# SeguidorC1_0.net
KiCad netlist of a schematic drawn in EAGLE
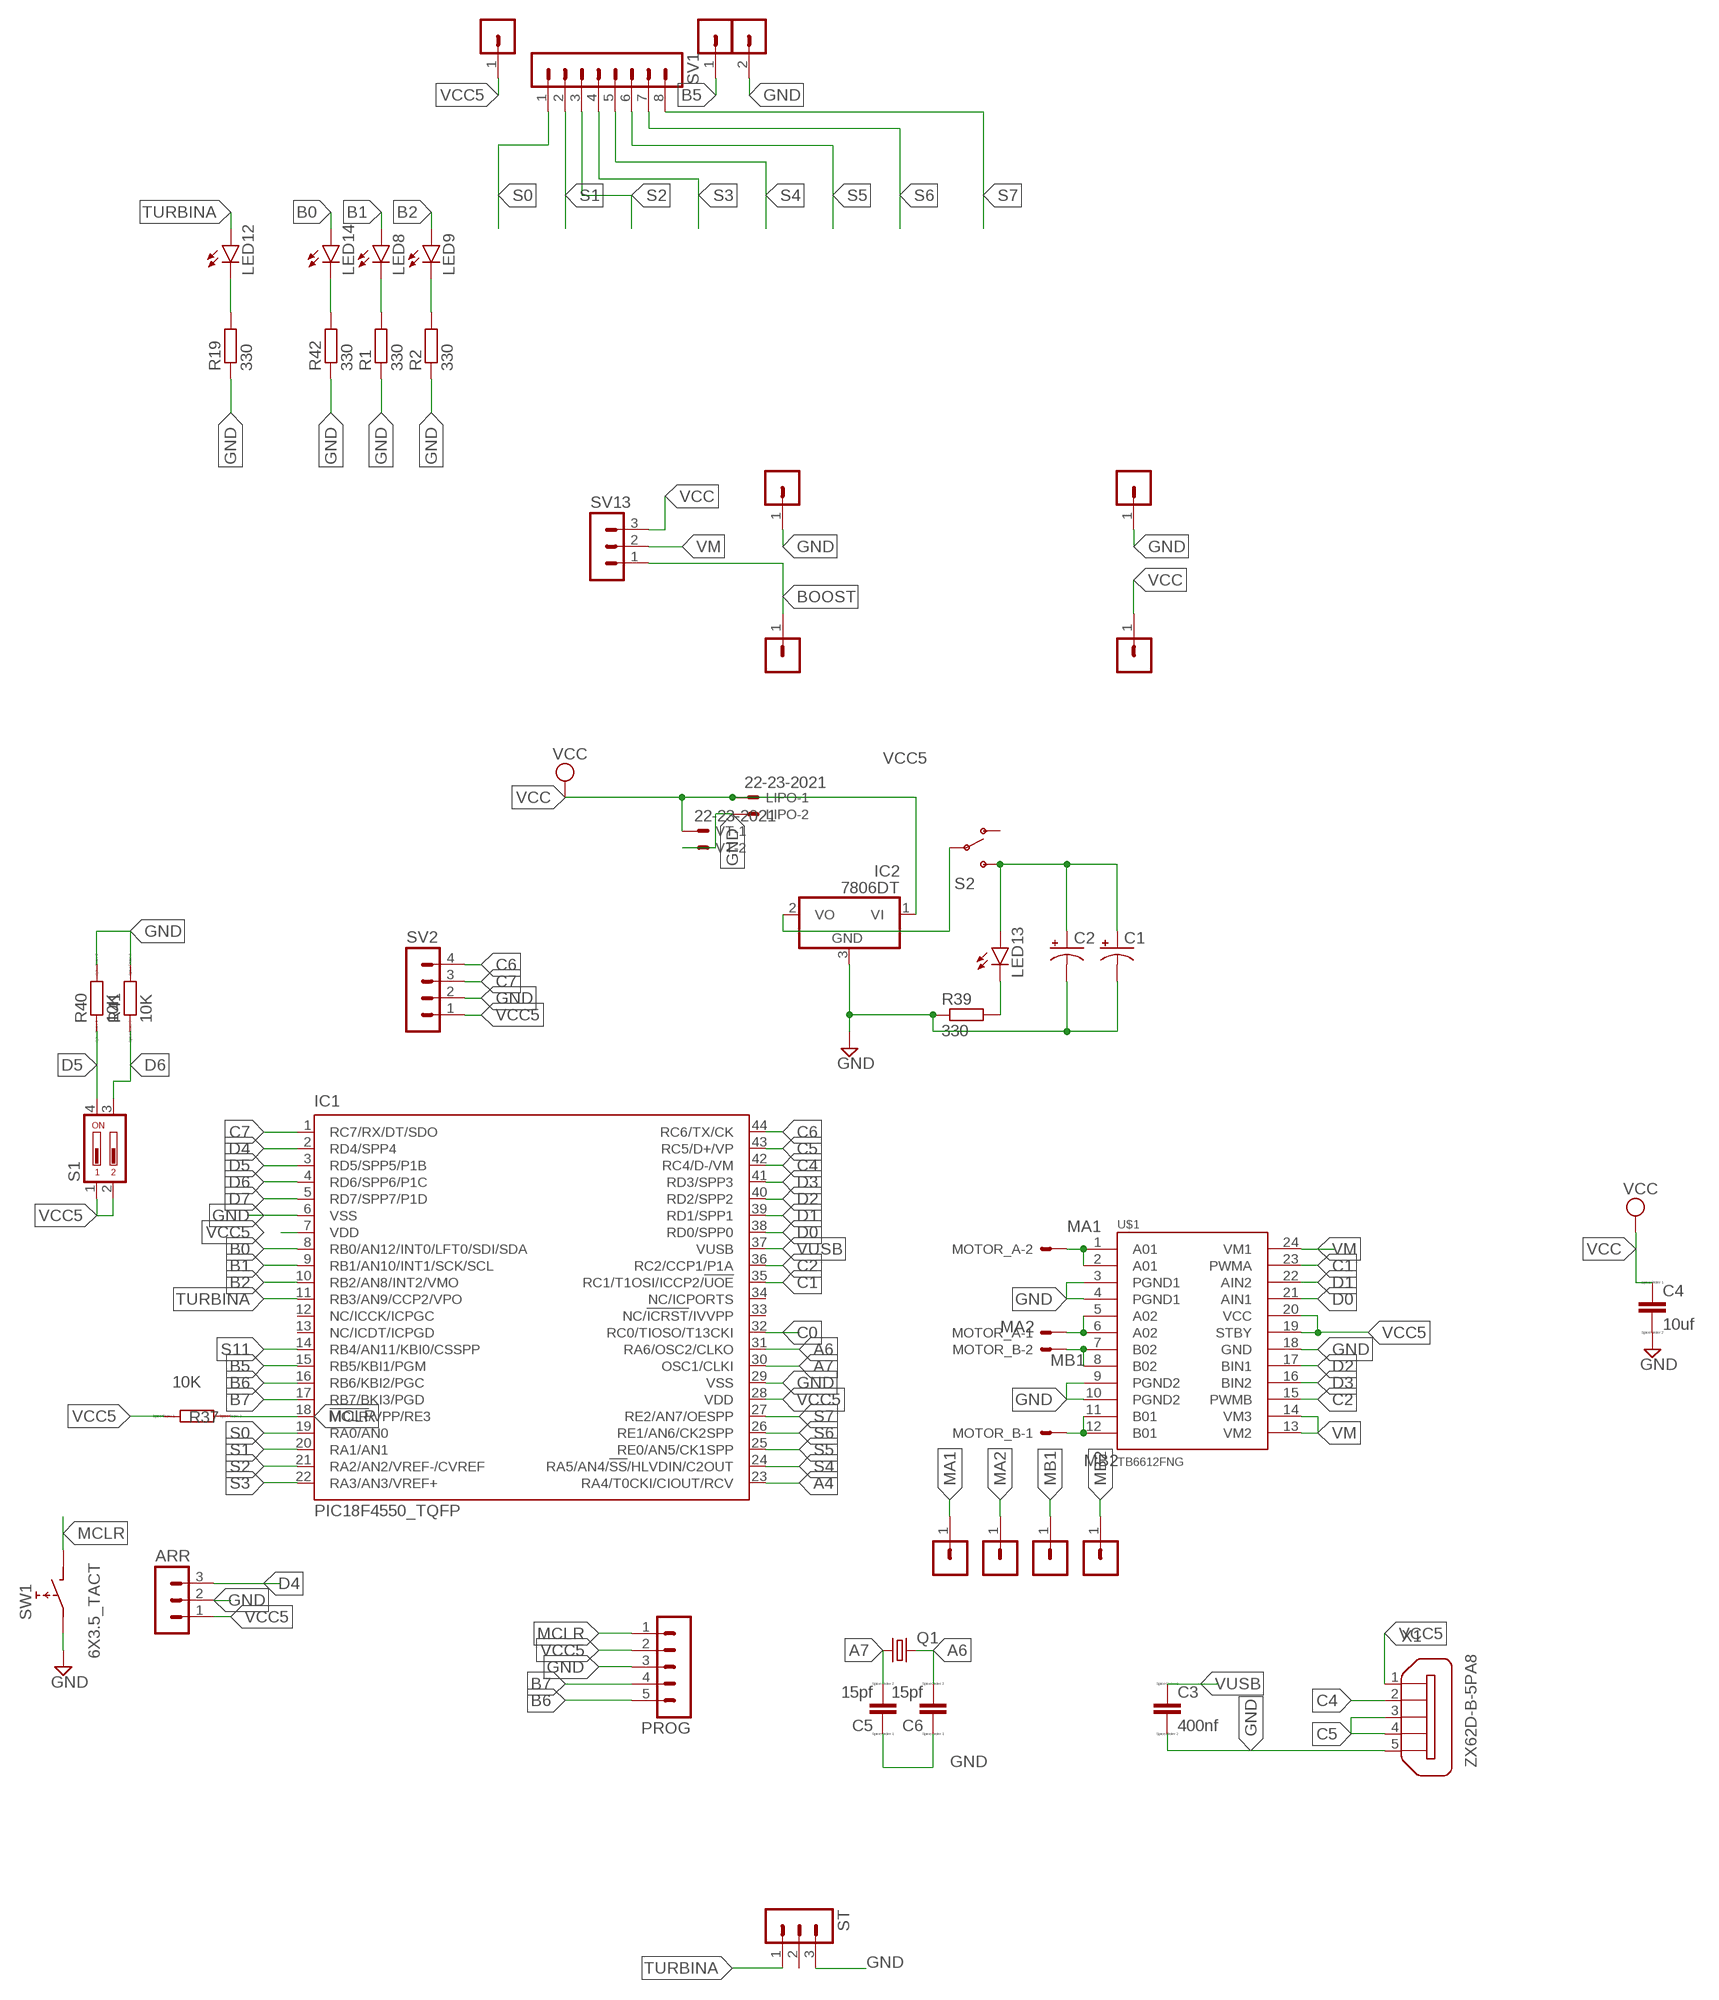
[diagram p0: schematic, sheet 1]

(export (version "E")
  (design (tool "Eeschema 10.0.6"))
  (components
    (comp (ref "ARR")
      (value "MA03-1")
      (footprint "eagle-import:MA03-1")
      (libsource (lib "eagle-import") (part "con-lstb_162_MA03-1"))
    )
    (comp (ref "C1")
      (value "CPOL-US153CLV-0505")
      (footprint "eagle-import:153CLV-0505")
      (libsource (lib "eagle-import") (part "CPOL-US153CLV-0505"))
    )
    (comp (ref "C2")
      (value "CPOL-US153CLV-0505")
      (footprint "eagle-import:153CLV-0505")
      (libsource (lib "eagle-import") (part "CPOL-US153CLV-0505"))
    )
    (comp (ref "C3")
      (value "400nf")
      (footprint "eagle-import:C0805")
      (libsource (lib "eagle-import") (part "C"))
    )
    (comp (ref "C4")
      (value "10uf")
      (footprint "eagle-import:C0805")
      (libsource (lib "eagle-import") (part "C"))
    )
    (comp (ref "C5")
      (value "15pf")
      (footprint "eagle-import:C0805")
      (libsource (lib "eagle-import") (part "C"))
    )
    (comp (ref "C6")
      (value "15pf")
      (footprint "eagle-import:C0805")
      (libsource (lib "eagle-import") (part "C"))
    )
    (comp (ref "IC1")
      (value "PIC18F4550_TQFP")
      (footprint "eagle-import:TQFP44")
      (fields (field (name "MF") "MICROCHIP") (field (name "MPN") "PIC18F4550-I/PT"))
      (libsource (lib "eagle-import") (part "PIC18F4_TQFP550"))
    )
    (comp (ref "IC2")
      (value "7806DT")
      (footprint "eagle-import:TO252")
      (libsource (lib "eagle-import") (part "78DT06"))
    )
    (comp (ref "LED8")
      (value "LEDCHIP-LED0805")
      (footprint "eagle-import:CHIP-LED0805")
      (libsource (lib "eagle-import") (part "LEDCHIP-LED0805"))
    )
    (comp (ref "LED9")
      (value "LEDCHIP-LED0805")
      (footprint "eagle-import:CHIP-LED0805")
      (libsource (lib "eagle-import") (part "LEDCHIP-LED0805"))
    )
    (comp (ref "LED12")
      (value "LEDCHIP-LED0805")
      (footprint "eagle-import:CHIP-LED0805")
      (libsource (lib "eagle-import") (part "LEDCHIP-LED0805"))
    )
    (comp (ref "LED13")
      (value "LEDCHIP-LED0805")
      (footprint "eagle-import:CHIP-LED0805")
      (libsource (lib "eagle-import") (part "LEDCHIP-LED0805"))
    )
    (comp (ref "LED14")
      (value "LEDCHIP-LED0805")
      (footprint "eagle-import:CHIP-LED0805")
      (libsource (lib "eagle-import") (part "LEDCHIP-LED0805"))
    )
    (comp (ref "LIPO")
      (value "22-23-2021")
      (footprint "eagle-import:22-23-2021")
      (fields (field (name "MF") "MOLEX"))
      (libsource (lib "eagle-import") (part "22-23-2021"))
    )
    (comp (ref "MOTOR_A")
      (value "22-23-2021")
      (footprint "eagle-import:22-23-2021")
      (fields (field (name "MF") "MOLEX"))
      (libsource (lib "eagle-import") (part "22-23-2021"))
    )
    (comp (ref "MOTOR_B")
      (value "22-23-2021")
      (footprint "eagle-import:22-23-2021")
      (fields (field (name "MF") "MOLEX"))
      (libsource (lib "eagle-import") (part "22-23-2021"))
    )
    (comp (ref "PROG")
      (value "MA05-1")
      (footprint "eagle-import:MA05-1")
      (libsource (lib "eagle-import") (part "MA05-1"))
    )
    (comp (ref "Q1")
      (value "CRYSTALHC49U-V")
      (footprint "eagle-import:HC49U-V")
      (libsource (lib "eagle-import") (part "CRYSTALHC49U-V"))
    )
    (comp (ref "R1")
      (value "330")
      (footprint "eagle-import:R0805")
      (libsource (lib "eagle-import") (part "R-EU_R0805"))
    )
    (comp (ref "R2")
      (value "330")
      (footprint "eagle-import:R0805")
      (libsource (lib "eagle-import") (part "R-EU_R0805"))
    )
    (comp (ref "R19")
      (value "330")
      (footprint "eagle-import:R0805")
      (libsource (lib "eagle-import") (part "R-EU_R0805"))
    )
    (comp (ref "R37")
      (value "10K")
      (footprint "eagle-import:R0805")
      (libsource (lib "eagle-import") (part "R"))
    )
    (comp (ref "R39")
      (value "330")
      (footprint "eagle-import:R0805")
      (libsource (lib "eagle-import") (part "R-EU_R0805"))
    )
    (comp (ref "R40")
      (value "10K")
      (footprint "eagle-import:R0805")
      (libsource (lib "eagle-import") (part "R"))
    )
    (comp (ref "R41")
      (value "10K")
      (footprint "eagle-import:R0805")
      (libsource (lib "eagle-import") (part "R"))
    )
    (comp (ref "R42")
      (value "330")
      (footprint "eagle-import:R0805")
      (libsource (lib "eagle-import") (part "R-EU_R0805"))
    )
    (comp (ref "S1")
      (value "DIP02YL")
      (footprint "eagle-import:DIP02YL")
      (libsource (lib "eagle-import") (part "DIP02YL"))
    )
    (comp (ref "S2")
      (value "SWITCH-SPSTPTH")
      (footprint "eagle-import:SWITCH-SPDT")
      (libsource (lib "eagle-import") (part "SWITCH-SPSTPTH"))
    )
    (comp (ref "ST")
      (value "MA03-1")
      (footprint "eagle-import:MA03-1")
      (libsource (lib "eagle-import") (part "MA03-1"))
    )
    (comp (ref "SV1")
      (value "MA08-1")
      (footprint "eagle-import:MA08-1")
      (libsource (lib "eagle-import") (part "MA08-1"))
    )
    (comp (ref "SV2")
      (value "MA04-1")
      (footprint "eagle-import:MA04-1")
      (libsource (lib "eagle-import") (part "MA04-1"))
    )
    (comp (ref "SV3")
      (value "MA01-1")
      (footprint "eagle-import:MA01-1")
      (libsource (lib "eagle-import") (part "MA01-1"))
    )
    (comp (ref "SV4")
      (value "MA01-1")
      (footprint "eagle-import:MA01-1")
      (libsource (lib "eagle-import") (part "MA01-1"))
    )
    (comp (ref "SV5")
      (value "MA01-1")
      (footprint "eagle-import:MA01-1")
      (libsource (lib "eagle-import") (part "MA01-1"))
    )
    (comp (ref "SV6")
      (value "MA01-1")
      (footprint "eagle-import:MA01-1")
      (libsource (lib "eagle-import") (part "MA01-1"))
    )
    (comp (ref "SV7")
      (value "MA01-1")
      (footprint "eagle-import:MA01-1")
      (libsource (lib "eagle-import") (part "MA01-1"))
    )
    (comp (ref "SV8")
      (value "MA02-1")
      (footprint "eagle-import:MA02-1")
      (libsource (lib "eagle-import") (part "MA02-1"))
    )
    (comp (ref "SV9")
      (value "MA01-1")
      (footprint "eagle-import:MA01-1")
      (libsource (lib "eagle-import") (part "MA01-1"))
    )
    (comp (ref "SV10")
      (value "MA01-1")
      (footprint "eagle-import:MA01-1")
      (libsource (lib "eagle-import") (part "MA01-1"))
    )
    (comp (ref "SV11")
      (value "MA01-1")
      (footprint "eagle-import:MA01-1")
      (libsource (lib "eagle-import") (part "MA01-1"))
    )
    (comp (ref "SV12")
      (value "MA01-1")
      (footprint "eagle-import:MA01-1")
      (libsource (lib "eagle-import") (part "MA01-1"))
    )
    (comp (ref "SV13")
      (value "MA03-1")
      (footprint "eagle-import:MA03-1")
      (libsource (lib "eagle-import") (part "MA03-1"))
    )
    (comp (ref "SW1")
      (value "6X3.5_TACT")
      (footprint "eagle-import:TACT_6X3.5")
      (libsource (lib "eagle-import") (part "6X3.5_TACT"))
    )
    (comp (ref "U$1")
      (value "TB6612FNG")
      (footprint "eagle-import:SSOP24")
      (libsource (lib "eagle-import") (part "TB6612FNG"))
    )
    (comp (ref "VT")
      (value "22-23-2021")
      (footprint "eagle-import:22-23-2021")
      (fields (field (name "MF") "MOLEX"))
      (libsource (lib "eagle-import") (part "22-23-2021"))
    )
    (comp (ref "X1")
      (value "ZX62D-B-5PA8")
      (footprint "eagle-import:ZX62D-B-5PA8")
      (fields (field (name "MF") "Hirose"))
      (libsource (lib "eagle-import") (part "ZX62D-B-5PA8"))
    )
  )
  (nets
    (net (code "1") (name "A4") (class "Default")
      (node (ref "IC1") (pin "23") (pinfunction "RA4/T0CKI/CIOUT/RCV_23") (pintype "bidirectional"))
    )
    (net (code "2") (name "A6") (class "Default")
      (node (ref "C6") (pin "2") (pinfunction "2_2") (pintype "passive"))
      (node (ref "IC1") (pin "31") (pinfunction "RA6/OSC2/CLKO_31") (pintype "output"))
      (node (ref "Q1") (pin "2") (pinfunction "2_2") (pintype "passive"))
    )
    (net (code "3") (name "A7") (class "Default")
      (node (ref "C5") (pin "2") (pinfunction "2_2") (pintype "passive"))
      (node (ref "IC1") (pin "30") (pinfunction "OSC1/CLKI_30") (pintype "input"))
      (node (ref "Q1") (pin "1") (pinfunction "1_1") (pintype "passive"))
    )
    (net (code "4") (name "B0") (class "Default")
      (node (ref "IC1") (pin "8") (pinfunction "RB0/AN12/INT0/LFT0/SDI/SDA_8") (pintype "bidirectional"))
      (node (ref "LED14") (pin "A") (pinfunction "A_A") (pintype "passive"))
    )
    (net (code "5") (name "B1") (class "Default")
      (node (ref "IC1") (pin "9") (pinfunction "RB1/AN10/INT1/SCK/SCL_9") (pintype "bidirectional"))
      (node (ref "LED8") (pin "A") (pinfunction "A_A") (pintype "passive"))
    )
    (net (code "6") (name "B2") (class "Default")
      (node (ref "IC1") (pin "10") (pinfunction "RB2/AN8/INT2/VMO_10") (pintype "bidirectional"))
      (node (ref "LED9") (pin "A") (pinfunction "A_A") (pintype "passive"))
    )
    (net (code "7") (name "B5") (class "Default")
      (node (ref "IC1") (pin "15") (pinfunction "RB5/KBI1/PGM_15") (pintype "bidirectional"))
      (node (ref "SV8") (pin "1") (pinfunction "1_1") (pintype "passive"))
    )
    (net (code "8") (name "B6") (class "Default")
      (node (ref "IC1") (pin "16") (pinfunction "RB6/KBI2/PGC_16") (pintype "bidirectional"))
      (node (ref "PROG") (pin "5") (pinfunction "5_5") (pintype "passive"))
    )
    (net (code "9") (name "B7") (class "Default")
      (node (ref "IC1") (pin "17") (pinfunction "RB7/BKI3/PGD_17") (pintype "bidirectional"))
      (node (ref "PROG") (pin "4") (pinfunction "4_4") (pintype "passive"))
    )
    (net (code "10") (name "BOOST") (class "Default")
      (node (ref "SV11") (pin "1") (pinfunction "3_1") (pintype "passive"))
      (node (ref "SV13") (pin "1") (pinfunction "1_1") (pintype "passive"))
    )
    (net (code "11") (name "C0") (class "Default")
      (node (ref "IC1") (pin "32") (pinfunction "RC0/TIOSO/T13CKI_32") (pintype "bidirectional"))
    )
    (net (code "12") (name "C1") (class "Default")
      (node (ref "IC1") (pin "35") (pinfunction "RC1/T1OSI/ICCP2/~{UOE}_35") (pintype "bidirectional"))
      (node (ref "U$1") (pin "23") (pinfunction "PWMA_23") (pintype "bidirectional"))
    )
    (net (code "13") (name "C2") (class "Default")
      (node (ref "IC1") (pin "36") (pinfunction "RC2/CCP1/P1A_36") (pintype "bidirectional"))
      (node (ref "U$1") (pin "15") (pinfunction "PWMB_15") (pintype "bidirectional"))
    )
    (net (code "14") (name "C4") (class "Default")
      (node (ref "IC1") (pin "42") (pinfunction "RC4/D-/VM_42") (pintype "bidirectional"))
      (node (ref "X1") (pin "2") (pinfunction "2_2") (pintype "passive"))
    )
    (net (code "15") (name "C5") (class "Default")
      (node (ref "IC1") (pin "43") (pinfunction "RC5/D+/VP_43") (pintype "bidirectional"))
      (node (ref "X1") (pin "3") (pinfunction "3_3") (pintype "passive"))
      (node (ref "X1") (pin "4") (pinfunction "4_4") (pintype "passive"))
    )
    (net (code "16") (name "C6") (class "Default")
      (node (ref "IC1") (pin "44") (pinfunction "RC6/TX/CK_44") (pintype "bidirectional"))
      (node (ref "SV2") (pin "4") (pinfunction "4_4") (pintype "passive"))
    )
    (net (code "17") (name "C7") (class "Default")
      (node (ref "IC1") (pin "1") (pinfunction "RC7/RX/DT/SDO_1") (pintype "bidirectional"))
      (node (ref "SV2") (pin "3") (pinfunction "3_3") (pintype "passive"))
    )
    (net (code "18") (name "D0") (class "Default")
      (node (ref "IC1") (pin "38") (pinfunction "RD0/SPP0_38") (pintype "bidirectional"))
      (node (ref "U$1") (pin "21") (pinfunction "AIN1_21") (pintype "bidirectional"))
    )
    (net (code "19") (name "D1") (class "Default")
      (node (ref "IC1") (pin "39") (pinfunction "RD1/SPP1_39") (pintype "bidirectional"))
      (node (ref "U$1") (pin "22") (pinfunction "AIN2_22") (pintype "bidirectional"))
    )
    (net (code "20") (name "D2") (class "Default")
      (node (ref "IC1") (pin "40") (pinfunction "RD2/SPP2_40") (pintype "bidirectional"))
      (node (ref "U$1") (pin "17") (pinfunction "BIN1_17") (pintype "bidirectional"))
    )
    (net (code "21") (name "D3") (class "Default")
      (node (ref "IC1") (pin "41") (pinfunction "RD3/SPP3_41") (pintype "bidirectional"))
      (node (ref "U$1") (pin "16") (pinfunction "BIN2_16") (pintype "bidirectional"))
    )
    (net (code "22") (name "D4") (class "Default")
      (node (ref "ARR") (pin "3") (pinfunction "3_3") (pintype "passive"))
      (node (ref "IC1") (pin "2") (pinfunction "RD4/SPP4_2") (pintype "bidirectional"))
    )
    (net (code "23") (name "D5") (class "Default")
      (node (ref "IC1") (pin "3") (pinfunction "RD5/SPP5/P1B_3") (pintype "bidirectional"))
      (node (ref "R40") (pin "1") (pinfunction "1_1") (pintype "passive"))
      (node (ref "S1") (pin "4") (pinfunction "4_4") (pintype "passive"))
    )
    (net (code "24") (name "D6") (class "Default")
      (node (ref "IC1") (pin "4") (pinfunction "RD6/SPP6/P1C_4") (pintype "bidirectional"))
      (node (ref "R41") (pin "1") (pinfunction "1_1") (pintype "passive"))
      (node (ref "S1") (pin "3") (pinfunction "3_3") (pintype "passive"))
    )
    (net (code "25") (name "D7") (class "Default")
      (node (ref "IC1") (pin "5") (pinfunction "RD7/SPP7/P1D_5") (pintype "bidirectional"))
    )
    (net (code "26") (name "GND") (class "Default")
      (node (ref "ARR") (pin "2") (pinfunction "2_2") (pintype "passive"))
      (node (ref "C1") (pin "-") (pinfunction "-_-") (pintype "passive"))
      (node (ref "C2") (pin "-") (pinfunction "-_-") (pintype "passive"))
      (node (ref "C3") (pin "2") (pinfunction "2_2") (pintype "passive"))
      (node (ref "C4") (pin "2") (pinfunction "2_2") (pintype "passive"))
      (node (ref "C5") (pin "1") (pinfunction "1_1") (pintype "passive"))
      (node (ref "C6") (pin "1") (pinfunction "1_1") (pintype "passive"))
      (node (ref "IC1") (pin "29") (pinfunction "VSS_29") (pintype "power_in"))
      (node (ref "IC1") (pin "6") (pinfunction "VSS_6") (pintype "power_in"))
      (node (ref "IC2") (pin "3") (pinfunction "GND_3") (pintype "passive"))
      (node (ref "LIPO") (pin "2") (pinfunction "S_2") (pintype "passive"))
      (node (ref "PROG") (pin "3") (pinfunction "3_3") (pintype "passive"))
      (node (ref "R1") (pin "1") (pinfunction "1_1") (pintype "passive"))
      (node (ref "R19") (pin "1") (pinfunction "1_1") (pintype "passive"))
      (node (ref "R2") (pin "1") (pinfunction "1_1") (pintype "passive"))
      (node (ref "R39") (pin "1") (pinfunction "1_1") (pintype "passive"))
      (node (ref "R40") (pin "2") (pinfunction "2_2") (pintype "passive"))
      (node (ref "R41") (pin "2") (pinfunction "2_2") (pintype "passive"))
      (node (ref "R42") (pin "1") (pinfunction "1_1") (pintype "passive"))
      (node (ref "ST") (pin "3") (pinfunction "3_3") (pintype "passive"))
      (node (ref "SV10") (pin "1") (pinfunction "3_1") (pintype "passive"))
      (node (ref "SV2") (pin "2") (pinfunction "2_2") (pintype "passive"))
      (node (ref "SV8") (pin "2") (pinfunction "3_2") (pintype "passive"))
      (node (ref "SV9") (pin "1") (pinfunction "3_1") (pintype "passive"))
      (node (ref "SW1") (pin "P$1") (pinfunction "1_P$1") (pintype "passive"))
      (node (ref "U$1") (pin "10") (pinfunction "PGND2_10") (pintype "bidirectional"))
      (node (ref "U$1") (pin "18") (pinfunction "GND_18") (pintype "bidirectional"))
      (node (ref "U$1") (pin "3") (pinfunction "PGND1_3") (pintype "bidirectional"))
      (node (ref "U$1") (pin "4") (pinfunction "PGND1_4") (pintype "bidirectional"))
      (node (ref "U$1") (pin "9") (pinfunction "PGND2_9") (pintype "bidirectional"))
      (node (ref "VT") (pin "2") (pinfunction "S_2") (pintype "passive"))
      (node (ref "X1") (pin "5") (pinfunction "5_5") (pintype "passive"))
    )
    (net (code "27") (name "MA1") (class "Default")
      (node (ref "MOTOR_A") (pin "2") (pinfunction "S_2") (pintype "passive"))
      (node (ref "SV3") (pin "1") (pinfunction "3_1") (pintype "passive"))
      (node (ref "U$1") (pin "1") (pinfunction "A01_1") (pintype "bidirectional"))
      (node (ref "U$1") (pin "2") (pinfunction "A01_2") (pintype "bidirectional"))
    )
    (net (code "28") (name "MA2") (class "Default")
      (node (ref "MOTOR_A") (pin "1") (pinfunction "S_1") (pintype "passive"))
      (node (ref "SV4") (pin "1") (pinfunction "3_1") (pintype "passive"))
      (node (ref "U$1") (pin "5") (pinfunction "A02_5") (pintype "bidirectional"))
      (node (ref "U$1") (pin "6") (pinfunction "A02_6") (pintype "bidirectional"))
    )
    (net (code "29") (name "MB1") (class "Default")
      (node (ref "MOTOR_B") (pin "2") (pinfunction "S_2") (pintype "passive"))
      (node (ref "SV5") (pin "1") (pinfunction "3_1") (pintype "passive"))
      (node (ref "U$1") (pin "7") (pinfunction "B02_7") (pintype "bidirectional"))
      (node (ref "U$1") (pin "8") (pinfunction "B02_8") (pintype "bidirectional"))
    )
    (net (code "30") (name "MB2") (class "Default")
      (node (ref "MOTOR_B") (pin "1") (pinfunction "S_1") (pintype "passive"))
      (node (ref "SV6") (pin "1") (pinfunction "3_1") (pintype "passive"))
      (node (ref "U$1") (pin "11") (pinfunction "B01_11") (pintype "bidirectional"))
      (node (ref "U$1") (pin "12") (pinfunction "B01_12") (pintype "bidirectional"))
    )
    (net (code "31") (name "MCLR") (class "Default")
      (node (ref "IC1") (pin "18") (pinfunction "~{MCLR}/VPP/RE3_18") (pintype "input"))
      (node (ref "PROG") (pin "1") (pinfunction "1_1") (pintype "passive"))
      (node (ref "R37") (pin "2") (pinfunction "2_2") (pintype "passive"))
      (node (ref "SW1") (pin "P$2") (pinfunction "2_P$2") (pintype "passive"))
    )
    (net (code "32") (name "Net-(IC2-VO)") (class "Default")
      (node (ref "IC2") (pin "2") (pinfunction "VO_2") (pintype "passive"))
      (node (ref "S2") (pin "2") (pinfunction "P_2") (pintype "passive"))
    )
    (net (code "33") (name "Net-(LED8-PadC)") (class "Default")
      (node (ref "LED8") (pin "C") (pinfunction "C_C") (pintype "passive"))
      (node (ref "R1") (pin "2") (pinfunction "2_2") (pintype "passive"))
    )
    (net (code "34") (name "Net-(LED9-PadC)") (class "Default")
      (node (ref "LED9") (pin "C") (pinfunction "C_C") (pintype "passive"))
      (node (ref "R2") (pin "2") (pinfunction "2_2") (pintype "passive"))
    )
    (net (code "35") (name "Net-(LED12-PadC)") (class "Default")
      (node (ref "LED12") (pin "C") (pinfunction "C_C") (pintype "passive"))
      (node (ref "R19") (pin "2") (pinfunction "2_2") (pintype "passive"))
    )
    (net (code "36") (name "Net-(LED13-PadC)") (class "Default")
      (node (ref "LED13") (pin "C") (pinfunction "C_C") (pintype "passive"))
      (node (ref "R39") (pin "2") (pinfunction "2_2") (pintype "passive"))
    )
    (net (code "37") (name "Net-(LED14-PadC)") (class "Default")
      (node (ref "LED14") (pin "C") (pinfunction "C_C") (pintype "passive"))
      (node (ref "R42") (pin "2") (pinfunction "2_2") (pintype "passive"))
    )
    (net (code "38") (name "S0") (class "Default")
      (node (ref "IC1") (pin "19") (pinfunction "RA0/AN0_19") (pintype "bidirectional"))
      (node (ref "SV1") (pin "1") (pinfunction "1_1") (pintype "passive"))
    )
    (net (code "39") (name "S1") (class "Default")
      (node (ref "IC1") (pin "20") (pinfunction "RA1/AN1_20") (pintype "bidirectional"))
      (node (ref "SV1") (pin "2") (pinfunction "2_2") (pintype "passive"))
    )
    (net (code "40") (name "S2") (class "Default")
      (node (ref "IC1") (pin "21") (pinfunction "RA2/AN2/VREF-/CVREF_21") (pintype "bidirectional"))
      (node (ref "SV1") (pin "3") (pinfunction "3_3") (pintype "passive"))
    )
    (net (code "41") (name "S3") (class "Default")
      (node (ref "IC1") (pin "22") (pinfunction "RA3/AN3/VREF+_22") (pintype "bidirectional"))
      (node (ref "SV1") (pin "4") (pinfunction "4_4") (pintype "passive"))
    )
    (net (code "42") (name "S4") (class "Default")
      (node (ref "IC1") (pin "24") (pinfunction "RA5/AN4/~{SS}/HLVDIN/C2OUT_24") (pintype "bidirectional"))
      (node (ref "SV1") (pin "5") (pinfunction "5_5") (pintype "passive"))
    )
    (net (code "43") (name "S5") (class "Default")
      (node (ref "IC1") (pin "25") (pinfunction "RE0/AN5/CK1SPP_25") (pintype "bidirectional"))
      (node (ref "SV1") (pin "6") (pinfunction "6_6") (pintype "passive"))
    )
    (net (code "44") (name "S6") (class "Default")
      (node (ref "IC1") (pin "26") (pinfunction "RE1/AN6/CK2SPP_26") (pintype "bidirectional"))
      (node (ref "SV1") (pin "7") (pinfunction "7_7") (pintype "passive"))
    )
    (net (code "45") (name "S7") (class "Default")
      (node (ref "IC1") (pin "27") (pinfunction "RE2/AN7/OESPP_27") (pintype "bidirectional"))
      (node (ref "SV1") (pin "8") (pinfunction "8_8") (pintype "passive"))
    )
    (net (code "46") (name "S11") (class "Default")
      (node (ref "IC1") (pin "14") (pinfunction "RB4/AN11/KBI0/CSSPP_14") (pintype "bidirectional"))
    )
    (net (code "47") (name "TURBINA") (class "Default")
      (node (ref "IC1") (pin "11") (pinfunction "RB3/AN9/CCP2/VPO_11") (pintype "bidirectional"))
      (node (ref "LED12") (pin "A") (pinfunction "A_A") (pintype "passive"))
      (node (ref "ST") (pin "1") (pinfunction "1_1") (pintype "passive"))
    )
    (net (code "48") (name "VCC") (class "Default")
      (node (ref "C4") (pin "1") (pinfunction "1_1") (pintype "passive"))
      (node (ref "IC2") (pin "1") (pinfunction "VI_1") (pintype "input"))
      (node (ref "LIPO") (pin "1") (pinfunction "S_1") (pintype "passive"))
      (node (ref "SV12") (pin "1") (pinfunction "3_1") (pintype "passive"))
      (node (ref "SV13") (pin "3") (pinfunction "3_3") (pintype "passive"))
      (node (ref "VT") (pin "1") (pinfunction "S_1") (pintype "passive"))
    )
    (net (code "49") (name "VCC5") (class "Default")
      (node (ref "ARR") (pin "1") (pinfunction "1_1") (pintype "passive"))
      (node (ref "C1") (pin "+") (pinfunction "+_+") (pintype "passive"))
      (node (ref "C2") (pin "+") (pinfunction "+_+") (pintype "passive"))
      (node (ref "IC1") (pin "28") (pinfunction "VDD_28") (pintype "power_in"))
      (node (ref "IC1") (pin "7") (pinfunction "VDD_7") (pintype "power_in"))
      (node (ref "LED13") (pin "A") (pinfunction "A_A") (pintype "passive"))
      (node (ref "PROG") (pin "2") (pinfunction "2_2") (pintype "passive"))
      (node (ref "R37") (pin "1") (pinfunction "1_1") (pintype "passive"))
      (node (ref "S1") (pin "1") (pinfunction "1_1") (pintype "passive"))
      (node (ref "S1") (pin "2") (pinfunction "2_2") (pintype "passive"))
      (node (ref "S2") (pin "3") (pinfunction "S_3") (pintype "passive"))
      (node (ref "SV2") (pin "1") (pinfunction "1_1") (pintype "passive"))
      (node (ref "SV7") (pin "1") (pinfunction "3_1") (pintype "passive"))
      (node (ref "U$1") (pin "19") (pinfunction "STBY_19") (pintype "bidirectional"))
      (node (ref "U$1") (pin "20") (pinfunction "VCC_20") (pintype "bidirectional"))
      (node (ref "X1") (pin "1") (pinfunction "1_1") (pintype "passive"))
    )
    (net (code "50") (name "VM") (class "Default")
      (node (ref "SV13") (pin "2") (pinfunction "2_2") (pintype "passive"))
      (node (ref "U$1") (pin "13") (pinfunction "VM2_13") (pintype "bidirectional"))
      (node (ref "U$1") (pin "14") (pinfunction "VM3_14") (pintype "bidirectional"))
      (node (ref "U$1") (pin "24") (pinfunction "VM1_24") (pintype "bidirectional"))
    )
    (net (code "51") (name "VUSB") (class "Default")
      (node (ref "C3") (pin "1") (pinfunction "1_1") (pintype "passive"))
      (node (ref "IC1") (pin "37") (pinfunction "VUSB_37") (pintype "bidirectional"))
    )
    (net (code "52") (name "unconnected-(IC1-NC{slash}ICCK{slash}ICPGC-Pad12)") (class "Default")
      (node (ref "IC1") (pin "12") (pinfunction "NC/ICCK/ICPGC_12") (pintype "bidirectional"))
    )
    (net (code "53") (name "unconnected-(IC1-NC{slash}ICDT{slash}ICPGD-Pad13)") (class "Default")
      (node (ref "IC1") (pin "13") (pinfunction "NC/ICDT/ICPGD_13") (pintype "bidirectional"))
    )
    (net (code "54") (name "unconnected-(IC1-NC{slash}ICPORTS-Pad34)") (class "Default")
      (node (ref "IC1") (pin "34") (pinfunction "NC/ICPORTS_34") (pintype "input"))
    )
    (net (code "55") (name "unconnected-(IC1-NC{slash}~{ICRST}{slash}IVVPP-Pad33)") (class "Default")
      (node (ref "IC1") (pin "33") (pinfunction "NC/~{ICRST}/IVVPP_33") (pintype "input"))
    )
    (net (code "56") (name "unconnected-(S2-O-Pad1)") (class "Default")
      (node (ref "S2") (pin "1") (pinfunction "O_1") (pintype "passive"))
    )
    (net (code "57") (name "unconnected-(ST-Pad2)") (class "Default")
      (node (ref "ST") (pin "2") (pinfunction "2_2") (pintype "passive"))
    )
  )
)
